# signalConditioner.net
KiCad netlist of a schematic drawn in EAGLE
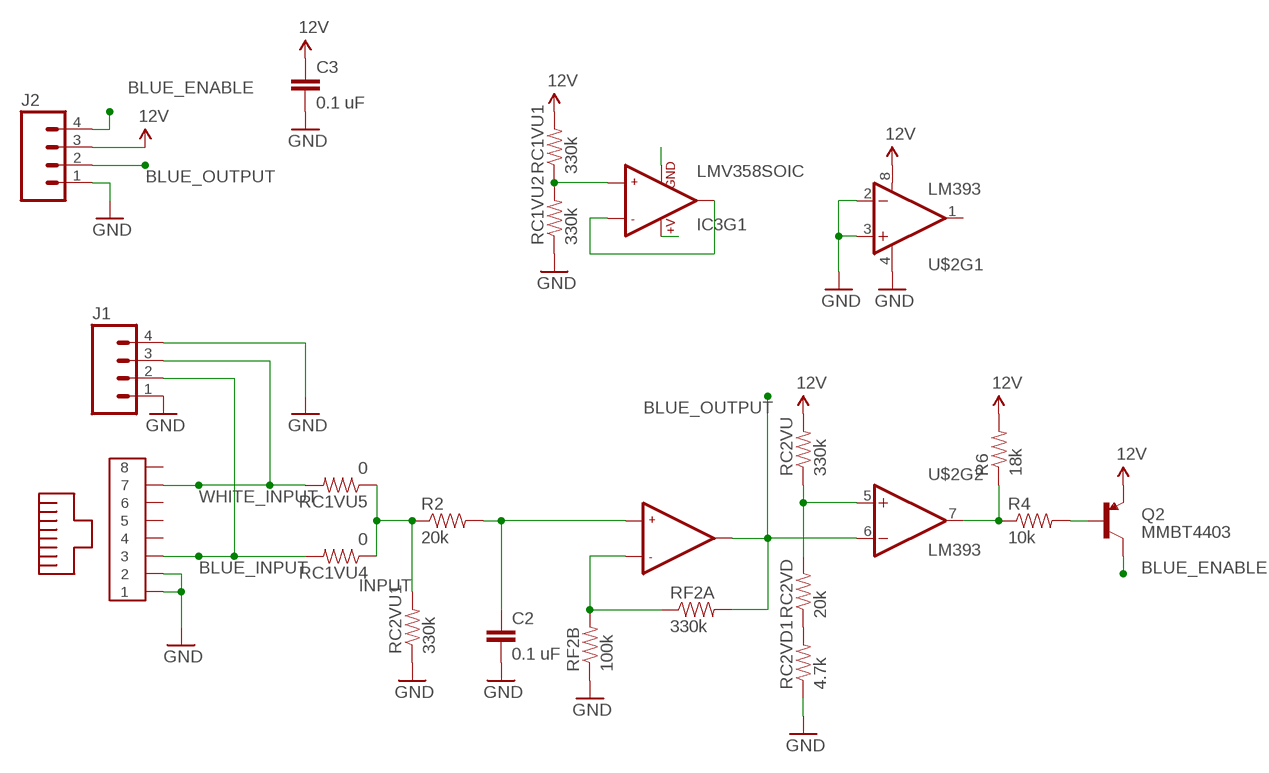
[diagram p0: schematic, sheet 1]

(export (version "E")
  (design (tool "Eeschema 10.0.6"))
  (components
    (comp (ref "C2")
      (value "0.1 uF")
      (footprint "eagle-import:1206")
      (libsource (lib "eagle-import") (part "CAP1206"))
    )
    (comp (ref "C3")
      (value "0.1 uF")
      (footprint "eagle-import:1206")
      (libsource (lib "eagle-import") (part "CAP1206"))
    )
    (comp (ref "IC3")
      (value "LMV358SOIC")
      (footprint "eagle-import:SO08")
      (libsource (lib "eagle-import") (part "LMV358SOIC"))
    )
    (comp (ref "J1")
      (value "M04LONGPADS")
      (footprint "eagle-import:1X04_LONGPADS")
      (libsource (lib "eagle-import") (part "M04LONGPADS"))
    )
    (comp (ref "J2")
      (value "M04LONGPADS")
      (footprint "eagle-import:1X04_LONGPADS")
      (libsource (lib "eagle-import") (part "M04LONGPADS"))
    )
    (comp (ref "Q2")
      (value "MMBT4403")
      (footprint "eagle-import:SOT23-3")
      (libsource (lib "eagle-import") (part "TRANSISTOR_PNPMMBT4403"))
    )
    (comp (ref "R2")
      (value "20k")
      (footprint "eagle-import:1206")
      (libsource (lib "eagle-import") (part "RESISTOR1206"))
    )
    (comp (ref "R4")
      (value "10k")
      (footprint "eagle-import:1206")
      (libsource (lib "eagle-import") (part "RESISTOR1206"))
    )
    (comp (ref "R6")
      (value "18k")
      (footprint "eagle-import:1206")
      (libsource (lib "eagle-import") (part "RESISTOR1206"))
    )
    (comp (ref "RC1VU1")
      (value "330k")
      (footprint "eagle-import:1206")
      (libsource (lib "eagle-import") (part "RESISTOR1206"))
    )
    (comp (ref "RC1VU2")
      (value "330k")
      (footprint "eagle-import:1206")
      (libsource (lib "eagle-import") (part "RESISTOR1206"))
    )
    (comp (ref "RC1VU4")
      (value "0")
      (footprint "eagle-import:1206")
      (libsource (lib "eagle-import") (part "RESISTOR1206"))
    )
    (comp (ref "RC1VU5")
      (value "0")
      (footprint "eagle-import:1206")
      (libsource (lib "eagle-import") (part "RESISTOR1206"))
    )
    (comp (ref "RC2VD")
      (value "20k")
      (footprint "eagle-import:1206")
      (libsource (lib "eagle-import") (part "RESISTOR1206"))
    )
    (comp (ref "RC2VD1")
      (value "4.7k")
      (footprint "eagle-import:1206")
      (libsource (lib "eagle-import") (part "RESISTOR1206"))
    )
    (comp (ref "RC2VU")
      (value "330k")
      (footprint "eagle-import:1206")
      (libsource (lib "eagle-import") (part "RESISTOR1206"))
    )
    (comp (ref "RC2VU1")
      (value "330k")
      (footprint "eagle-import:1206")
      (libsource (lib "eagle-import") (part "RESISTOR1206"))
    )
    (comp (ref "RF2A")
      (value "330k")
      (footprint "eagle-import:1206")
      (libsource (lib "eagle-import") (part "RESISTOR1206"))
    )
    (comp (ref "RF2B")
      (value "100k")
      (footprint "eagle-import:1206")
      (libsource (lib "eagle-import") (part "RESISTOR1206"))
    )
    (comp (ref "U$1")
      (value "MOLEX-RJ45-SMT")
      (footprint "eagle-import:MOLEX-RJ45-SMT")
      (libsource (lib "eagle-import") (part "MOLEX-RJ45-SMT"))
    )
    (comp (ref "U$2")
      (value "LM393")
      (footprint "eagle-import:SO08")
      (libsource (lib "eagle-import") (part "LM393"))
    )
  )
  (nets
    (net (code "1") (name "/BLUE_ENABLE") (class "Default")
      (node (ref "J2") (pin "4") (pinfunction "4_4") (pintype "passive"))
      (node (ref "Q2") (pin "3") (pinfunction "C_3") (pintype "passive"))
    )
    (net (code "2") (name "/BLUE_INPUT") (class "Default")
      (node (ref "J1") (pin "2") (pinfunction "2_2") (pintype "passive"))
      (node (ref "RC1VU4") (pin "2") (pinfunction "2_2") (pintype "passive"))
      (node (ref "U$1") (pin "3") (pinfunction "3_3") (pintype "bidirectional"))
    )
    (net (code "3") (name "/BLUE_OUTPUT") (class "Default")
      (node (ref "IC3") (pin "7") (pinfunction "OUT2_7") (pintype "output"))
      (node (ref "J2") (pin "2") (pinfunction "2_2") (pintype "passive"))
      (node (ref "RF2A") (pin "2") (pinfunction "2_2") (pintype "passive"))
      (node (ref "U$2") (pin "6") (pinfunction "-IN_6") (pintype "input"))
    )
    (net (code "4") (name "/INPUT") (class "Default")
      (node (ref "R2") (pin "1") (pinfunction "1_1") (pintype "passive"))
      (node (ref "RC1VU4") (pin "1") (pinfunction "1_1") (pintype "passive"))
      (node (ref "RC1VU5") (pin "1") (pinfunction "1_1") (pintype "passive"))
      (node (ref "RC2VU1") (pin "2") (pinfunction "2_2") (pintype "passive"))
    )
    (net (code "5") (name "/WHITE_INPUT") (class "Default")
      (node (ref "J1") (pin "3") (pinfunction "3_3") (pintype "passive"))
      (node (ref "RC1VU5") (pin "2") (pinfunction "2_2") (pintype "passive"))
      (node (ref "U$1") (pin "7") (pinfunction "7_7") (pintype "bidirectional"))
    )
    (net (code "6") (name "12V") (class "Default")
      (node (ref "C3") (pin "1") (pinfunction "1_1") (pintype "passive"))
      (node (ref "IC3") (pin "8") (pinfunction "+V_8") (pintype "power_in"))
      (node (ref "J2") (pin "3") (pinfunction "3_3") (pintype "passive"))
      (node (ref "Q2") (pin "2") (pinfunction "E_2") (pintype "passive"))
      (node (ref "R6") (pin "2") (pinfunction "2_2") (pintype "passive"))
      (node (ref "RC1VU1") (pin "2") (pinfunction "2_2") (pintype "passive"))
      (node (ref "RC2VU") (pin "2") (pinfunction "2_2") (pintype "passive"))
      (node (ref "U$2") (pin "8") (pinfunction "V+_8") (pintype "power_in"))
    )
    (net (code "7") (name "GND") (class "Default")
      (node (ref "C2") (pin "2") (pinfunction "2_2") (pintype "passive"))
      (node (ref "C3") (pin "2") (pinfunction "2_2") (pintype "passive"))
      (node (ref "IC3") (pin "4") (pinfunction "GND_4") (pintype "power_in"))
      (node (ref "J1") (pin "1") (pinfunction "1_1") (pintype "passive"))
      (node (ref "J1") (pin "4") (pinfunction "4_4") (pintype "passive"))
      (node (ref "J2") (pin "1") (pinfunction "1_1") (pintype "passive"))
      (node (ref "RC1VU2") (pin "1") (pinfunction "1_1") (pintype "passive"))
      (node (ref "RC2VD1") (pin "1") (pinfunction "1_1") (pintype "passive"))
      (node (ref "RC2VU1") (pin "1") (pinfunction "1_1") (pintype "passive"))
      (node (ref "RF2B") (pin "1") (pinfunction "1_1") (pintype "passive"))
      (node (ref "U$1") (pin "1") (pinfunction "1_1") (pintype "bidirectional"))
      (node (ref "U$1") (pin "2") (pinfunction "2_2") (pintype "bidirectional"))
      (node (ref "U$2") (pin "2") (pinfunction "-IN_2") (pintype "input"))
      (node (ref "U$2") (pin "3") (pinfunction "+IN_3") (pintype "input"))
      (node (ref "U$2") (pin "4") (pinfunction "V-_4") (pintype "power_in"))
    )
    (net (code "8") (name "Net-(IC3A-+IN1)") (class "Default")
      (node (ref "IC3") (pin "3") (pinfunction "+IN1_3") (pintype "input"))
      (node (ref "RC1VU1") (pin "1") (pinfunction "1_1") (pintype "passive"))
      (node (ref "RC1VU2") (pin "2") (pinfunction "2_2") (pintype "passive"))
    )
    (net (code "9") (name "Net-(IC3A--IN1)") (class "Default")
      (node (ref "IC3") (pin "1") (pinfunction "OUT1_1") (pintype "output"))
      (node (ref "IC3") (pin "2") (pinfunction "-IN1_2") (pintype "input"))
    )
    (net (code "10") (name "Net-(IC3B-+IN2)") (class "Default")
      (node (ref "C2") (pin "1") (pinfunction "1_1") (pintype "passive"))
      (node (ref "IC3") (pin "5") (pinfunction "+IN2_5") (pintype "input"))
      (node (ref "R2") (pin "2") (pinfunction "2_2") (pintype "passive"))
    )
    (net (code "11") (name "Net-(IC3B--IN2)") (class "Default")
      (node (ref "IC3") (pin "6") (pinfunction "-IN2_6") (pintype "input"))
      (node (ref "RF2A") (pin "1") (pinfunction "1_1") (pintype "passive"))
      (node (ref "RF2B") (pin "2") (pinfunction "2_2") (pintype "passive"))
    )
    (net (code "12") (name "Net-(Q2-B)") (class "Default")
      (node (ref "Q2") (pin "1") (pinfunction "B_1") (pintype "passive"))
      (node (ref "R4") (pin "2") (pinfunction "2_2") (pintype "passive"))
    )
    (net (code "13") (name "Net-(RC2VD-Pad1)") (class "Default")
      (node (ref "RC2VD") (pin "1") (pinfunction "1_1") (pintype "passive"))
      (node (ref "RC2VD1") (pin "2") (pinfunction "2_2") (pintype "passive"))
    )
    (net (code "14") (name "Net-(U$2B-+IN)") (class "Default")
      (node (ref "RC2VD") (pin "2") (pinfunction "2_2") (pintype "passive"))
      (node (ref "RC2VU") (pin "1") (pinfunction "1_1") (pintype "passive"))
      (node (ref "U$2") (pin "5") (pinfunction "+IN_5") (pintype "input"))
    )
    (net (code "15") (name "Net-(U$2B-OUT)") (class "Default")
      (node (ref "R4") (pin "1") (pinfunction "1_1") (pintype "passive"))
      (node (ref "R6") (pin "1") (pinfunction "1_1") (pintype "passive"))
      (node (ref "U$2") (pin "7") (pinfunction "OUT_7") (pintype "output"))
    )
    (net (code "16") (name "unconnected-(U$1-Pad4)") (class "Default")
      (node (ref "U$1") (pin "4") (pinfunction "4_4") (pintype "bidirectional"))
    )
    (net (code "17") (name "unconnected-(U$1-Pad5)") (class "Default")
      (node (ref "U$1") (pin "5") (pinfunction "5_5") (pintype "bidirectional"))
    )
    (net (code "18") (name "unconnected-(U$1-Pad6)") (class "Default")
      (node (ref "U$1") (pin "6") (pinfunction "6_6") (pintype "bidirectional"))
    )
    (net (code "19") (name "unconnected-(U$1-Pad8)") (class "Default")
      (node (ref "U$1") (pin "8") (pinfunction "8_8") (pintype "bidirectional"))
    )
    (net (code "20") (name "unconnected-(U$2A-OUT-Pad1)") (class "Default")
      (node (ref "U$2") (pin "1") (pinfunction "OUT_1") (pintype "output"))
    )
  )
)
